# Schematic_EBook_v19.net
KiCad netlist of a schematic drawn in EAGLE
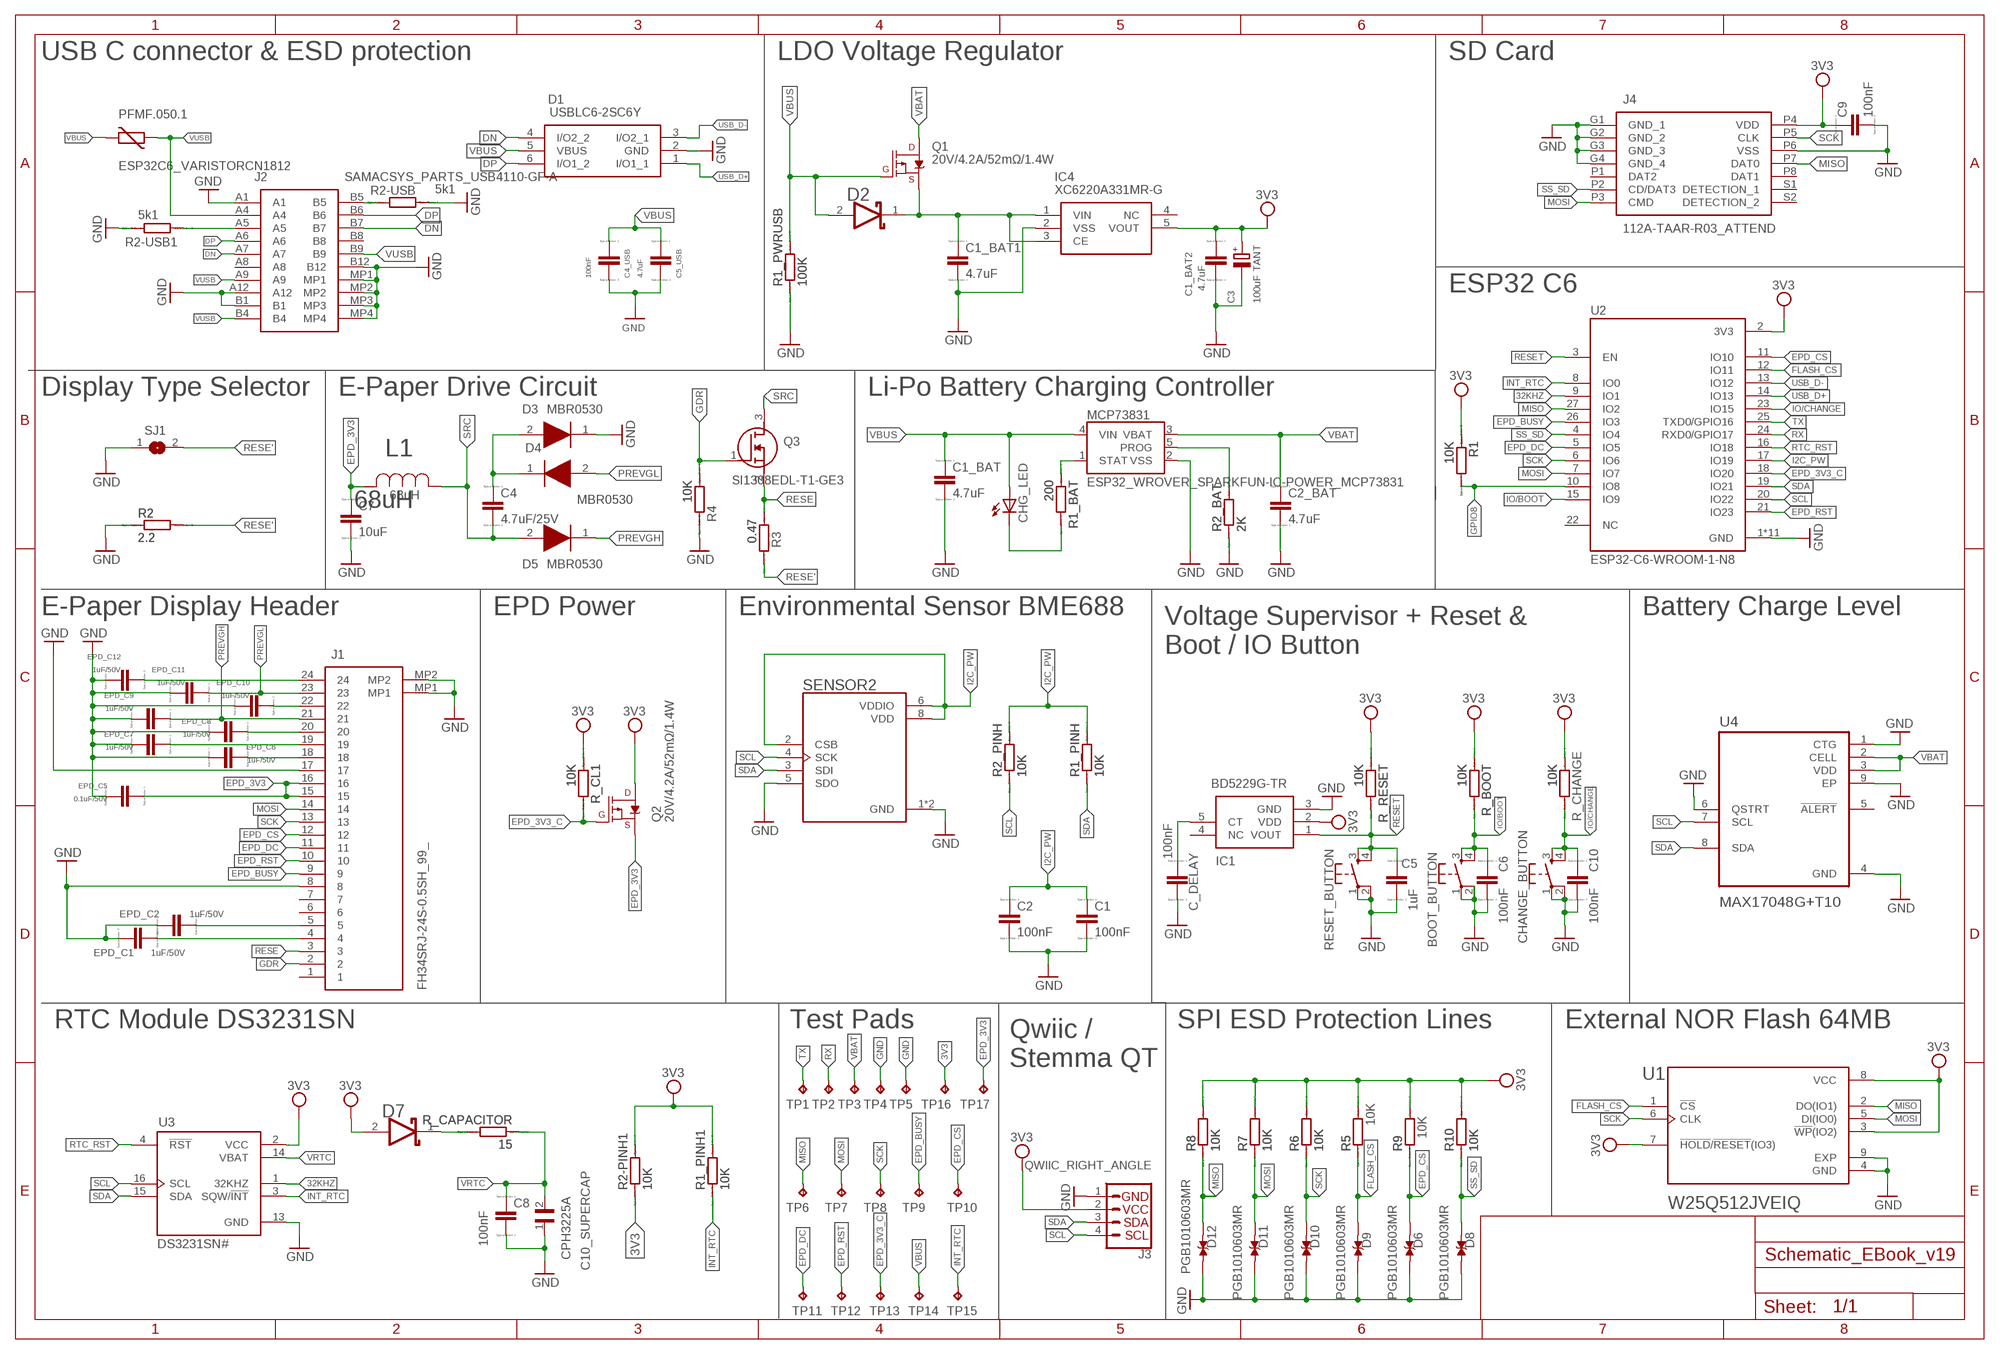
[diagram p0: schematic, sheet 1]

(export (version "E")
  (design (tool "Eeschema 10.0.6"))
  (components
    (comp (ref "BOOT_BUTTON")
      (value "BUTTON_CUSYOMV1")
      (footprint "eagle-import:MYBUTTON")
      (libsource (lib "eagle-import") (part "BUTTON_CUSYOMV1"))
    )
    (comp (ref "C1")
      (value "100nF")
      (footprint "eagle-import:EAGLE-LTSPICE_C0402")
      (libsource (lib "eagle-import") (part "EAGLE-LTSPICE_CC0402"))
    )
    (comp (ref "C1_BAT")
      (value "4.7uF")
      (footprint "eagle-import:EAGLE-LTSPICE_C0402")
      (libsource (lib "eagle-import") (part "EAGLE-LTSPICE_CC0402"))
    )
    (comp (ref "C1_BAT1")
      (value "4.7uF")
      (footprint "eagle-import:EAGLE-LTSPICE_C0402")
      (libsource (lib "eagle-import") (part "EAGLE-LTSPICE_CC0402"))
    )
    (comp (ref "C1_BAT2")
      (value "4.7uF")
      (footprint "eagle-import:EAGLE-LTSPICE_C0402")
      (libsource (lib "eagle-import") (part "ESP32_WROVER_EAGLE-LTSPICE_CC0402"))
    )
    (comp (ref "C2")
      (value "100nF")
      (footprint "eagle-import:EAGLE-LTSPICE_C0402")
      (libsource (lib "eagle-import") (part "EAGLE-LTSPICE_CC0402"))
    )
    (comp (ref "C2_BAT")
      (value "4.7uF")
      (footprint "eagle-import:EAGLE-LTSPICE_C0402")
      (libsource (lib "eagle-import") (part "EAGLE-LTSPICE_CC0402"))
    )
    (comp (ref "C3")
      (value "100uF TANT")
      (footprint "eagle-import:RCL_CT3528")
      (libsource (lib "eagle-import") (part "RCL_CPOL-EUCT3528"))
    )
    (comp (ref "C4")
      (value "4.7uF/25V")
      (footprint "eagle-import:EAGLE-LTSPICE_C0402")
      (libsource (lib "eagle-import") (part "EAGLE-LTSPICE_CC0402"))
    )
    (comp (ref "C4_USB")
      (value "100nF")
      (footprint "eagle-import:EAGLE-LTSPICE_C0402")
      (libsource (lib "eagle-import") (part "EAGLE-LTSPICE_CC0402"))
    )
    (comp (ref "C5")
      (value "1uF")
      (footprint "eagle-import:EAGLE-LTSPICE_C0402")
      (libsource (lib "eagle-import") (part "EAGLE-LTSPICE_CC0402"))
    )
    (comp (ref "C5_USB")
      (value "4.7uF")
      (footprint "eagle-import:EAGLE-LTSPICE_C0402")
      (libsource (lib "eagle-import") (part "EAGLE-LTSPICE_CC0402"))
    )
    (comp (ref "C6")
      (value "100nF")
      (footprint "eagle-import:EAGLE-LTSPICE_C0402")
      (libsource (lib "eagle-import") (part "EAGLE-LTSPICE_CC0402"))
    )
    (comp (ref "C7")
      (value "10uF")
      (footprint "eagle-import:EAGLE-LTSPICE_C0402")
      (libsource (lib "eagle-import") (part "EAGLE-LTSPICE_CC0402"))
    )
    (comp (ref "C8")
      (value "100nF")
      (footprint "eagle-import:EAGLE-LTSPICE_C0402")
      (libsource (lib "eagle-import") (part "EAGLE-LTSPICE_CC0402"))
    )
    (comp (ref "C9")
      (value "100nF")
      (footprint "eagle-import:EAGLE-LTSPICE_C0402")
      (libsource (lib "eagle-import") (part "EAGLE-LTSPICE_CC0402"))
    )
    (comp (ref "C10")
      (value "100nF")
      (footprint "eagle-import:EAGLE-LTSPICE_C0402")
      (libsource (lib "eagle-import") (part "EAGLE-LTSPICE_CC0402"))
    )
    (comp (ref "C10_SUPERCAP")
      (value "CPH3225A")
      (footprint "eagle-import:CAPCP3225X100N")
      (fields (field (name "MF") "Seiko Instruments"))
      (libsource (lib "eagle-import") (part "CPH3225A"))
    )
    (comp (ref "CHANGE_BUTTON")
      (value "BUTTON_CUSYOMV1")
      (footprint "eagle-import:MYBUTTON")
      (libsource (lib "eagle-import") (part "BUTTON_CUSYOMV1"))
    )
    (comp (ref "CHG_LED")
      (value "ADAFRUIT_LEDCHIP-LED0603")
      (footprint "eagle-import:ADAFRUIT_CHIP-LED0603")
      (libsource (lib "eagle-import") (part "ADAFRUIT_LEDCHIP-LED0603"))
    )
    (comp (ref "C_DELAY")
      (value "100nF")
      (footprint "eagle-import:EAGLE-LTSPICE_C0402")
      (libsource (lib "eagle-import") (part "EAGLE-LTSPICE_CC0402"))
    )
    (comp (ref "D1")
      (value "USBLC6-2SC6Y")
      (footprint "eagle-import:SOT95P280X145-6N")
      (fields (field (name "MF") "STMicroelectronics"))
      (libsource (lib "eagle-import") (part "USBLC6-2SC6Y"))
    )
    (comp (ref "D2")
      (value "ESP32_WROVER_AVX---SD0805S020S1R0_AVX_SD0805S020S1R0_0_0AVX_SD0805S020S1R0_0_0")
      (footprint "eagle-import:ESP32_WROVER_AVX---SD0805S020S1R0_AVX_SD0805S020S1R0_0")
      (fields
        (field (name "DIGIKEY_PART_NUMBER") "478-7800-1-ND")
        (field (name "MF") "AVX")
        (field (name "MOUSER_PART_NUMBER") "581-SD0805S020S1R0")
      )
      (libsource (lib "eagle-import") (part "ESP32_WROVER_AVX---SD0805S020S1R0_AVX_SD0805S020S1R0_0_0AVX_SD0805S020S1R0_0_0"))
    )
    (comp (ref "D3")
      (value "MBR0530")
      (footprint "eagle-import:SOD3716X135N")
      (fields (field (name "MF") "ON Semiconductor"))
      (libsource (lib "eagle-import") (part "MBR0530"))
    )
    (comp (ref "D4")
      (value "MBR0530")
      (footprint "eagle-import:SOD3716X135N")
      (fields (field (name "MF") "ON Semiconductor"))
      (libsource (lib "eagle-import") (part "MBR0530"))
    )
    (comp (ref "D5")
      (value "MBR0530")
      (footprint "eagle-import:SOD3716X135N")
      (fields (field (name "MF") "ON Semiconductor"))
      (libsource (lib "eagle-import") (part "MBR0530"))
    )
    (comp (ref "D6")
      (value "PGB1010603MR")
      (footprint "eagle-import:DIOC1608X36N")
      (fields (field (name "MF") "Littelfuse Inc."))
      (libsource (lib "eagle-import") (part "PGB1010603MR"))
    )
    (comp (ref "D7")
      (value "ESP32_WROVER_AVX---SD0805S020S1R0_AVX_SD0805S020S1R0_0_0AVX_SD0805S020S1R0_0_0")
      (footprint "eagle-import:ESP32_WROVER_AVX---SD0805S020S1R0_AVX_SD0805S020S1R0_0")
      (fields
        (field (name "DIGIKEY_PART_NUMBER") "478-7800-1-ND")
        (field (name "MF") "AVX")
        (field (name "MOUSER_PART_NUMBER") "581-SD0805S020S1R0")
      )
      (libsource (lib "eagle-import") (part "ESP32_WROVER_AVX---SD0805S020S1R0_AVX_SD0805S020S1R0_0_0AVX_SD0805S020S1R0_0_0"))
    )
    (comp (ref "D8")
      (value "PGB1010603MR")
      (footprint "eagle-import:DIOC1608X36N")
      (fields (field (name "MF") "Littelfuse Inc."))
      (libsource (lib "eagle-import") (part "PGB1010603MR"))
    )
    (comp (ref "D9")
      (value "PGB1010603MR")
      (footprint "eagle-import:DIOC1608X36N")
      (fields (field (name "MF") "Littelfuse Inc."))
      (libsource (lib "eagle-import") (part "PGB1010603MR"))
    )
    (comp (ref "D10")
      (value "PGB1010603MR")
      (footprint "eagle-import:DIOC1608X36N")
      (fields (field (name "MF") "Littelfuse Inc."))
      (libsource (lib "eagle-import") (part "PGB1010603MR"))
    )
    (comp (ref "D11")
      (value "PGB1010603MR")
      (footprint "eagle-import:DIOC1608X36N")
      (fields (field (name "MF") "Littelfuse Inc."))
      (libsource (lib "eagle-import") (part "PGB1010603MR"))
    )
    (comp (ref "D12")
      (value "PGB1010603MR")
      (footprint "eagle-import:DIOC1608X36N")
      (fields (field (name "MF") "Littelfuse Inc."))
      (libsource (lib "eagle-import") (part "PGB1010603MR"))
    )
    (comp (ref "EPD_C1")
      (value "1uF/50V")
      (footprint "eagle-import:EAGLE-LTSPICE_C0402")
      (libsource (lib "eagle-import") (part "EAGLE-LTSPICE_CC0402"))
    )
    (comp (ref "EPD_C2")
      (value "1uF/50V")
      (footprint "eagle-import:EAGLE-LTSPICE_C0402")
      (libsource (lib "eagle-import") (part "EAGLE-LTSPICE_CC0402"))
    )
    (comp (ref "EPD_C5")
      (value "0.1uF/50V")
      (footprint "eagle-import:EAGLE-LTSPICE_C0402")
      (libsource (lib "eagle-import") (part "EAGLE-LTSPICE_CC0402"))
    )
    (comp (ref "EPD_C6")
      (value "1uF/50V")
      (footprint "eagle-import:EAGLE-LTSPICE_C0402")
      (libsource (lib "eagle-import") (part "EAGLE-LTSPICE_CC0402"))
    )
    (comp (ref "EPD_C7")
      (value "1uF/50V")
      (footprint "eagle-import:EAGLE-LTSPICE_C0402")
      (libsource (lib "eagle-import") (part "EAGLE-LTSPICE_CC0402"))
    )
    (comp (ref "EPD_C8")
      (value "1uF/50V")
      (footprint "eagle-import:EAGLE-LTSPICE_C0402")
      (libsource (lib "eagle-import") (part "EAGLE-LTSPICE_CC0402"))
    )
    (comp (ref "EPD_C9")
      (value "1uF/50V")
      (footprint "eagle-import:EAGLE-LTSPICE_C0402")
      (libsource (lib "eagle-import") (part "EAGLE-LTSPICE_CC0402"))
    )
    (comp (ref "EPD_C10")
      (value "1uF/50V")
      (footprint "eagle-import:EAGLE-LTSPICE_C0402")
      (libsource (lib "eagle-import") (part "EAGLE-LTSPICE_CC0402"))
    )
    (comp (ref "EPD_C11")
      (value "1uF/50V")
      (footprint "eagle-import:EAGLE-LTSPICE_C0402")
      (libsource (lib "eagle-import") (part "EAGLE-LTSPICE_CC0402"))
    )
    (comp (ref "EPD_C12")
      (value "1uF/50V")
      (footprint "eagle-import:EAGLE-LTSPICE_C0402")
      (libsource (lib "eagle-import") (part "EAGLE-LTSPICE_CC0402"))
    )
    (comp (ref "IC1")
      (value "BD5229G-TR")
      (footprint "eagle-import:SOT95P280X125-5N")
      (fields (field (name "MOUSER_PART_NUMBER") "755-BD5229G-TR"))
      (libsource (lib "eagle-import") (part "BD5229G-TR"))
    )
    (comp (ref "IC4")
      (value "XC6220A331MR-G")
      (footprint "eagle-import:SOT95P280X120-5N")
      (fields (field (name "MOUSER_PART_NUMBER") "865-XC6220A331MR-G"))
      (libsource (lib "eagle-import") (part "XC6220A331MR-G"))
    )
    (comp (ref "J1")
      (value "FH34SRJ-24S-0.5SH_99_")
      (footprint "eagle-import:FH34SRJ24S05SH99")
      (fields
        (field (name "MANUFACTURER_PART_NUMBER") "FH34SRJ-24S-0.5SH(99)")
        (field (name "MOUSER_PART_NUMBER") "798-FH34SRJ24S05SH99")
      )
      (libsource (lib "eagle-import") (part "FH34SRJ-24S-0.5SH_99_"))
    )
    (comp (ref "J2")
      (value "SAMACSYS_PARTS_USB4110-GF-A")
      (footprint "eagle-import:SAMACSYS_PARTS_USB4110GFA")
      (fields
        (field (name "MANUFACTURER_PART_NUMBER") "USB4110-GF-A")
        (field (name "MOUSER_PART_NUMBER") "640-USB4110-GF-A")
      )
      (libsource (lib "eagle-import") (part "SAMACSYS_PARTS_USB4110-GF-A"))
    )
    (comp (ref "J3")
      (value "QWIIC_RIGHT_ANGLE")
      (footprint "eagle-import:JST04_1MM_RA")
      (libsource (lib "eagle-import") (part "QWIIC_CONNECTORJS-1MM"))
    )
    (comp (ref "J4")
      (value "112A-TAAR-R03_ATTEND")
      (footprint "eagle-import:112ATAARR03ATTEND")
      (fields (field (name "MANUFACTURER_PART_NUMBER") "112A-TAAR-R03 ATTEND"))
      (libsource (lib "eagle-import") (part "112A-TAAR-R03_ATTEND"))
    )
    (comp (ref "L1")
      (value "68uH")
      (footprint "eagle-import:IND_4828-WE-TPC_WRE")
      (fields
        (field (name "MANUFACTURER_PART_NUMBER") "744043680")
        (field (name "COPYRIGHT") "Copyright (C) 2024 Ultra Librarian. All rights reserved.")
      )
      (libsource (lib "eagle-import") (part "744043680IND_4828-WE-TPC_WRE"))
    )
    (comp (ref "MCP73831")
      (value "ESP32_WROVER_SPARKFUN-IC-POWER_MCP73831")
      (footprint "eagle-import:ESP32_WROVER_SPARKFUN-IC-POWER_SOT23-5")
      (libsource (lib "eagle-import") (part "ESP32_WROVER_SPARKFUN-IC-POWER_MCP73831"))
    )
    (comp (ref "PFMF.050.1")
      (value "ESP32C6_VARISTORCN1812")
      (footprint "eagle-import:ESP32C6_VARISTOR_CT_CN1812")
      (libsource (lib "eagle-import") (part "ESP32C6_VARISTORCN1812"))
    )
    (comp (ref "Q1")
      (value "20V/4.2A/52mΩ/1.4W")
      (footprint "eagle-import:ESP32_WROVER_SPARKFUN-DISCRETESEMI_SOT23-3")
      (libsource (lib "eagle-import") (part "ESP32_WROVER_SPARKFUN-DISCRETESEMI_MOSFET_PCH-DMG2305UX-7"))
    )
    (comp (ref "Q2")
      (value "20V/4.2A/52mΩ/1.4W")
      (footprint "eagle-import:ESP32_WROVER_SPARKFUN-DISCRETESEMI_SOT23-3")
      (libsource (lib "eagle-import") (part "ESP32_WROVER_SPARKFUN-DISCRETESEMI_MOSFET_PCH-DMG2305UX-7"))
    )
    (comp (ref "Q3")
      (value "SI1308EDL-T1-GE3")
      (footprint "eagle-import:SOT65P210X110-3N")
      (fields (field (name "MF") "Vishay Siliconix"))
      (libsource (lib "eagle-import") (part "SI1308EDL-T1-GE3"))
    )
    (comp (ref "R1")
      (value "10K")
      (footprint "eagle-import:ESP32_WROVER_EAGLE-LTSPICE_R0402")
      (libsource (lib "eagle-import") (part "ESP32_WROVER_EAGLE-LTSPICE_RR0402"))
    )
    (comp (ref "R1_BAT")
      (value "200")
      (footprint "eagle-import:ESP32_WROVER_EAGLE-LTSPICE_R0402")
      (libsource (lib "eagle-import") (part "ESP32_WROVER_EAGLE-LTSPICE_RR0402"))
    )
    (comp (ref "R1_PINH")
      (value "10K")
      (footprint "eagle-import:ESP32_WROVER_EAGLE-LTSPICE_R0402")
      (libsource (lib "eagle-import") (part "ESP32_WROVER_EAGLE-LTSPICE_RR0402"))
    )
    (comp (ref "R1_PINH1")
      (value "10K")
      (footprint "eagle-import:ESP32_WROVER_EAGLE-LTSPICE_R0402")
      (libsource (lib "eagle-import") (part "ESP32_WROVER_EAGLE-LTSPICE_RR0402"))
    )
    (comp (ref "R1_PWRUSB")
      (value "100K")
      (footprint "eagle-import:ESP32_WROVER_EAGLE-LTSPICE_R0402")
      (libsource (lib "eagle-import") (part "ESP32_WROVER_EAGLE-LTSPICE_RR0402"))
    )
    (comp (ref "R2")
      (value "2.2")
      (footprint "eagle-import:ESP32_WROVER_EAGLE-LTSPICE_R0402")
      (libsource (lib "eagle-import") (part "ESP32_WROVER_EAGLE-LTSPICE_RR0402"))
    )
    (comp (ref "R2-PINH1")
      (value "10K")
      (footprint "eagle-import:ESP32_WROVER_EAGLE-LTSPICE_R0402")
      (libsource (lib "eagle-import") (part "ESP32_WROVER_EAGLE-LTSPICE_RR0402"))
    )
    (comp (ref "R2-USB")
      (value "5k1")
      (footprint "eagle-import:ESP32_WROVER_EAGLE-LTSPICE_R0402")
      (libsource (lib "eagle-import") (part "ESP32_WROVER_EAGLE-LTSPICE_RR0402"))
    )
    (comp (ref "R2-USB1")
      (value "5k1")
      (footprint "eagle-import:ESP32_WROVER_EAGLE-LTSPICE_R0402")
      (libsource (lib "eagle-import") (part "ESP32_WROVER_EAGLE-LTSPICE_RR0402"))
    )
    (comp (ref "R2_BAT")
      (value "2K")
      (footprint "eagle-import:ESP32_WROVER_EAGLE-LTSPICE_R0402")
      (libsource (lib "eagle-import") (part "ESP32_WROVER_EAGLE-LTSPICE_RR0402"))
    )
    (comp (ref "R2_PINH")
      (value "10K")
      (footprint "eagle-import:ESP32_WROVER_EAGLE-LTSPICE_R0402")
      (libsource (lib "eagle-import") (part "ESP32_WROVER_EAGLE-LTSPICE_RR0402"))
    )
    (comp (ref "R3")
      (value "0.47")
      (footprint "eagle-import:ESP32_WROVER_EAGLE-LTSPICE_R0402")
      (libsource (lib "eagle-import") (part "ESP32_WROVER_EAGLE-LTSPICE_RR0402"))
    )
    (comp (ref "R4")
      (value "10K")
      (footprint "eagle-import:ESP32_WROVER_EAGLE-LTSPICE_R0402")
      (libsource (lib "eagle-import") (part "ESP32_WROVER_EAGLE-LTSPICE_RR0402"))
    )
    (comp (ref "R5")
      (value "10K")
      (footprint "eagle-import:ESP32_WROVER_EAGLE-LTSPICE_R0402")
      (libsource (lib "eagle-import") (part "ESP32_WROVER_EAGLE-LTSPICE_RR0402"))
    )
    (comp (ref "R6")
      (value "10K")
      (footprint "eagle-import:ESP32_WROVER_EAGLE-LTSPICE_R0402")
      (libsource (lib "eagle-import") (part "ESP32_WROVER_EAGLE-LTSPICE_RR0402"))
    )
    (comp (ref "R7")
      (value "10K")
      (footprint "eagle-import:ESP32_WROVER_EAGLE-LTSPICE_R0402")
      (libsource (lib "eagle-import") (part "ESP32_WROVER_EAGLE-LTSPICE_RR0402"))
    )
    (comp (ref "R8")
      (value "10K")
      (footprint "eagle-import:ESP32_WROVER_EAGLE-LTSPICE_R0402")
      (libsource (lib "eagle-import") (part "ESP32_WROVER_EAGLE-LTSPICE_RR0402"))
    )
    (comp (ref "R9")
      (value "10K")
      (footprint "eagle-import:ESP32_WROVER_EAGLE-LTSPICE_R0402")
      (libsource (lib "eagle-import") (part "ESP32_WROVER_EAGLE-LTSPICE_RR0402"))
    )
    (comp (ref "R10")
      (value "10K")
      (footprint "eagle-import:ESP32_WROVER_EAGLE-LTSPICE_R0402")
      (libsource (lib "eagle-import") (part "ESP32_WROVER_EAGLE-LTSPICE_RR0402"))
    )
    (comp (ref "RESET_BUTTON")
      (value "BUTTON_CUSYOMV1")
      (footprint "eagle-import:MYBUTTON")
      (libsource (lib "eagle-import") (part "BUTTON_CUSYOMV1"))
    )
    (comp (ref "R_BOOT")
      (value "10K")
      (footprint "eagle-import:ESP32_WROVER_EAGLE-LTSPICE_R0402")
      (libsource (lib "eagle-import") (part "ESP32_WROVER_EAGLE-LTSPICE_RR0402"))
    )
    (comp (ref "R_CAPACITOR")
      (value "15")
      (footprint "eagle-import:ESP32_WROVER_EAGLE-LTSPICE_R0402")
      (libsource (lib "eagle-import") (part "ESP32_WROVER_EAGLE-LTSPICE_RR0402"))
    )
    (comp (ref "R_CHANGE")
      (value "10K")
      (footprint "eagle-import:ESP32_WROVER_EAGLE-LTSPICE_R0402")
      (libsource (lib "eagle-import") (part "ESP32_WROVER_EAGLE-LTSPICE_RR0402"))
    )
    (comp (ref "R_CL1")
      (value "10K")
      (footprint "eagle-import:ESP32_WROVER_EAGLE-LTSPICE_R0402")
      (libsource (lib "eagle-import") (part "ESP32_WROVER_EAGLE-LTSPICE_RR0402"))
    )
    (comp (ref "R_RESET")
      (value "10K")
      (footprint "eagle-import:ESP32_WROVER_EAGLE-LTSPICE_R0402")
      (libsource (lib "eagle-import") (part "ESP32_WROVER_EAGLE-LTSPICE_RR0402"))
    )
    (comp (ref "SENSOR2")
      (value "ESP32_WROVER_BME680_BME680")
      (footprint "eagle-import:ESP32_WROVER_BME680_PSON80P300X300X100-8N")
      (fields (field (name "MF") "Bosch Sensortec") (field (name "MP") "BME680"))
      (libsource (lib "eagle-import") (part "ESP32_WROVER_BME680_BME680"))
    )
    (comp (ref "SJ1") (value "SJ") (footprint "eagle-import:SJ") (libsource (lib "eagle-import") (part "SJ")))
    (comp (ref "TP1")
      (value "TPTP20R")
      (footprint "eagle-import:TP20R")
      (libsource (lib "eagle-import") (part "TPTP20R"))
    )
    (comp (ref "TP2")
      (value "TPTP20R")
      (footprint "eagle-import:TP20R")
      (libsource (lib "eagle-import") (part "TPTP20R"))
    )
    (comp (ref "TP3")
      (value "TPTP20R")
      (footprint "eagle-import:TP20R")
      (libsource (lib "eagle-import") (part "TPTP20R"))
    )
    (comp (ref "TP4")
      (value "TPTP20R")
      (footprint "eagle-import:TP20R")
      (libsource (lib "eagle-import") (part "TPTP20R"))
    )
    (comp (ref "TP5")
      (value "TPTP20R")
      (footprint "eagle-import:TP20R")
      (libsource (lib "eagle-import") (part "TPTP20R"))
    )
    (comp (ref "TP6")
      (value "TPTP20R")
      (footprint "eagle-import:TP20R")
      (libsource (lib "eagle-import") (part "TPTP20R"))
    )
    (comp (ref "TP7")
      (value "TPTP20R")
      (footprint "eagle-import:TP20R")
      (libsource (lib "eagle-import") (part "TPTP20R"))
    )
    (comp (ref "TP8")
      (value "TPTP20R")
      (footprint "eagle-import:TP20R")
      (libsource (lib "eagle-import") (part "TPTP20R"))
    )
    (comp (ref "TP9")
      (value "TPTP20R")
      (footprint "eagle-import:TP20R")
      (libsource (lib "eagle-import") (part "TPTP20R"))
    )
    (comp (ref "TP10")
      (value "TPTP20R")
      (footprint "eagle-import:TP20R")
      (libsource (lib "eagle-import") (part "TPTP20R"))
    )
    (comp (ref "TP11")
      (value "TPTP20R")
      (footprint "eagle-import:TP20R")
      (libsource (lib "eagle-import") (part "TPTP20R"))
    )
    (comp (ref "TP12")
      (value "TPTP20R")
      (footprint "eagle-import:TP20R")
      (libsource (lib "eagle-import") (part "TPTP20R"))
    )
    (comp (ref "TP13")
      (value "TPTP20R")
      (footprint "eagle-import:TP20R")
      (libsource (lib "eagle-import") (part "TPTP20R"))
    )
    (comp (ref "TP14")
      (value "TPTP20R")
      (footprint "eagle-import:TP20R")
      (libsource (lib "eagle-import") (part "TPTP20R"))
    )
    (comp (ref "TP15")
      (value "TPTP20R")
      (footprint "eagle-import:TP20R")
      (libsource (lib "eagle-import") (part "TPTP20R"))
    )
    (comp (ref "TP16")
      (value "TPTP20R")
      (footprint "eagle-import:TP20R")
      (libsource (lib "eagle-import") (part "TPTP20R"))
    )
    (comp (ref "TP17")
      (value "TPTP20R")
      (footprint "eagle-import:TP20R")
      (libsource (lib "eagle-import") (part "TPTP20R"))
    )
    (comp (ref "U1")
      (value "W25Q512JVEIQ")
      (footprint "eagle-import:SON127P600X800X80-9N")
      (fields (field (name "MF") "Winbond Electronics"))
      (libsource (lib "eagle-import") (part "W25Q512JVEIQ"))
    )
    (comp (ref "U2")
      (value "ESP32-C6-WROOM-1-N8")
      (footprint "eagle-import:XCVR_ESP32-C6-WROOM-1-N8")
      (fields (field (name "MF") "Espressif Systems"))
      (libsource (lib "eagle-import") (part "ESP32-C6-WROOM-1-N8"))
    )
    (comp (ref "U3")
      (value "DS3231SN#")
      (footprint "eagle-import:SOIC127P1032X265-16N")
      (fields (field (name "MF") "Analog Devices"))
      (libsource (lib "eagle-import") (part "DS3231SN#"))
    )
    (comp (ref "U4")
      (value "MAX17048G+T10")
      (footprint "eagle-import:SON50P200X200X80-9N")
      (fields (field (name "MF") "Analog Devices"))
      (libsource (lib "eagle-import") (part "MAX17048G+T10"))
    )
  )
  (nets
    (net (code "1") (name "3V3") (class "Default")
      (node (ref "C1_BAT2") (pin "1") (pinfunction "1_1") (pintype "passive"))
      (node (ref "C3") (pin "+") (pinfunction "+_+") (pintype "passive"))
      (node (ref "C9") (pin "1") (pinfunction "1_1") (pintype "passive"))
      (node (ref "D7") (pin "2") (pinfunction "ANODE_2") (pintype "bidirectional"))
      (node (ref "IC1") (pin "2") (pinfunction "VDD_2") (pintype "bidirectional"))
      (node (ref "IC4") (pin "5") (pinfunction "VOUT_5") (pintype "bidirectional"))
      (node (ref "J3") (pin "2") (pinfunction "2_2") (pintype "power_in"))
      (node (ref "J4") (pin "P4") (pinfunction "VDD_P4") (pintype "bidirectional"))
      (node (ref "Q2") (pin "3") (pinfunction "D_3") (pintype "bidirectional"))
      (node (ref "R1") (pin "1") (pinfunction "1_1") (pintype "passive"))
      (node (ref "R10") (pin "2") (pinfunction "2_2") (pintype "passive"))
      (node (ref "R1_PINH1") (pin "2") (pinfunction "2_2") (pintype "passive"))
      (node (ref "R2-PINH1") (pin "1") (pinfunction "1_1") (pintype "passive"))
      (node (ref "R2-PINH1") (pin "2") (pinfunction "2_2") (pintype "passive"))
      (node (ref "R5") (pin "2") (pinfunction "2_2") (pintype "passive"))
      (node (ref "R6") (pin "2") (pinfunction "2_2") (pintype "passive"))
      (node (ref "R7") (pin "2") (pinfunction "2_2") (pintype "passive"))
      (node (ref "R8") (pin "2") (pinfunction "2_2") (pintype "passive"))
      (node (ref "R9") (pin "2") (pinfunction "2_2") (pintype "passive"))
      (node (ref "R_BOOT") (pin "1") (pinfunction "1_1") (pintype "passive"))
      (node (ref "R_CHANGE") (pin "1") (pinfunction "1_1") (pintype "passive"))
      (node (ref "R_CL1") (pin "1") (pinfunction "1_1") (pintype "passive"))
      (node (ref "R_RESET") (pin "1") (pinfunction "1_1") (pintype "passive"))
      (node (ref "TP16") (pin "TP") (pinfunction "TP_TP") (pintype "input"))
      (node (ref "U1") (pin "3") (pinfunction "~{WP}(IO2)_3") (pintype "bidirectional"))
      (node (ref "U1") (pin "7") (pinfunction "~{HOLD}/~{RESET}(IO3)_7") (pintype "bidirectional"))
      (node (ref "U1") (pin "8") (pinfunction "VCC_8") (pintype "power_in"))
      (node (ref "U2") (pin "2") (pinfunction "3V3_2") (pintype "power_in"))
      (node (ref "U3") (pin "2") (pinfunction "VCC_2") (pintype "power_in"))
    )
    (net (code "2") (name "32KHZ") (class "Default")
      (node (ref "U2") (pin "9") (pinfunction "IO1_9") (pintype "bidirectional"))
      (node (ref "U3") (pin "1") (pinfunction "32KHZ_1") (pintype "output"))
    )
    (net (code "3") (name "DN") (class "Default")
      (node (ref "D1") (pin "4") (pinfunction "I/O2_2_4") (pintype "bidirectional"))
      (node (ref "J2") (pin "A7") (pinfunction "A7_A7") (pintype "bidirectional"))
      (node (ref "J2") (pin "B7") (pinfunction "B7_B7") (pintype "bidirectional"))
    )
    (net (code "4") (name "DP") (class "Default")
      (node (ref "D1") (pin "6") (pinfunction "I/O1_2_6") (pintype "bidirectional"))
      (node (ref "J2") (pin "A6") (pinfunction "A6_A6") (pintype "bidirectional"))
      (node (ref "J2") (pin "B6") (pinfunction "B6_B6") (pintype "bidirectional"))
    )
    (net (code "5") (name "EPD_3V3") (class "Default")
      (node (ref "C7") (pin "1") (pinfunction "1_1") (pintype "passive"))
      (node (ref "EPD_C5") (pin "1") (pinfunction "1_1") (pintype "passive"))
      (node (ref "J1") (pin "15") (pinfunction "15_15") (pintype "bidirectional"))
      (node (ref "J1") (pin "16") (pinfunction "16_16") (pintype "bidirectional"))
      (node (ref "L1") (pin "2") (pinfunction "2_2") (pintype "passive"))
      (node (ref "Q2") (pin "2") (pinfunction "S_2") (pintype "bidirectional"))
      (node (ref "TP17") (pin "TP") (pinfunction "TP_TP") (pintype "input"))
    )
    (net (code "6") (name "EPD_3V3_C") (class "Default")
      (node (ref "Q2") (pin "1") (pinfunction "G_1") (pintype "bidirectional"))
      (node (ref "R_CL1") (pin "2") (pinfunction "2_2") (pintype "passive"))
      (node (ref "TP13") (pin "TP") (pinfunction "TP_TP") (pintype "input"))
      (node (ref "U2") (pin "18") (pinfunction "IO20_18") (pintype "bidirectional"))
    )
    (net (code "7") (name "EPD_BUSY") (class "Default")
      (node (ref "J1") (pin "9") (pinfunction "9_9") (pintype "bidirectional"))
      (node (ref "TP9") (pin "TP") (pinfunction "TP_TP") (pintype "input"))
      (node (ref "U2") (pin "26") (pinfunction "IO3_26") (pintype "bidirectional"))
    )
    (net (code "8") (name "EPD_CS") (class "Default")
      (node (ref "D6") (pin "2") (pinfunction "2_2") (pintype "passive"))
      (node (ref "J1") (pin "12") (pinfunction "12_12") (pintype "bidirectional"))
      (node (ref "R9") (pin "1") (pinfunction "1_1") (pintype "passive"))
      (node (ref "TP10") (pin "TP") (pinfunction "TP_TP") (pintype "input"))
      (node (ref "U2") (pin "11") (pinfunction "IO10_11") (pintype "bidirectional"))
    )
    (net (code "9") (name "EPD_DC") (class "Default")
      (node (ref "J1") (pin "11") (pinfunction "11_11") (pintype "bidirectional"))
      (node (ref "TP11") (pin "TP") (pinfunction "TP_TP") (pintype "input"))
      (node (ref "U2") (pin "5") (pinfunction "IO5_5") (pintype "bidirectional"))
    )
    (net (code "10") (name "EPD_RST") (class "Default")
      (node (ref "J1") (pin "10") (pinfunction "10_10") (pintype "bidirectional"))
      (node (ref "TP12") (pin "TP") (pinfunction "TP_TP") (pintype "input"))
      (node (ref "U2") (pin "21") (pinfunction "IO23_21") (pintype "bidirectional"))
    )
    (net (code "11") (name "FLASH_CS") (class "Default")
      (node (ref "D9") (pin "2") (pinfunction "2_2") (pintype "passive"))
      (node (ref "R5") (pin "1") (pinfunction "1_1") (pintype "passive"))
      (node (ref "U1") (pin "1") (pinfunction "~{CS}_1") (pintype "input"))
      (node (ref "U2") (pin "12") (pinfunction "IO11_12") (pintype "bidirectional"))
    )
    (net (code "12") (name "GDR") (class "Default")
      (node (ref "J1") (pin "2") (pinfunction "2_2") (pintype "bidirectional"))
      (node (ref "Q3") (pin "1") (pinfunction "G_1") (pintype "bidirectional"))
      (node (ref "R4") (pin "1") (pinfunction "1_1") (pintype "passive"))
    )
    (net (code "13") (name "GND") (class "Default")
      (node (ref "BOOT_BUTTON") (pin "1") (pinfunction "1_1") (pintype "passive"))
      (node (ref "BOOT_BUTTON") (pin "2") (pinfunction "2_2") (pintype "passive"))
      (node (ref "C1") (pin "2") (pinfunction "2_2") (pintype "passive"))
      (node (ref "C10") (pin "2") (pinfunction "2_2") (pintype "passive"))
      (node (ref "C10_SUPERCAP") (pin "1") (pinfunction "1_1") (pintype "passive"))
      (node (ref "C1_BAT") (pin "2") (pinfunction "2_2") (pintype "passive"))
      (node (ref "C1_BAT1") (pin "2") (pinfunction "2_2") (pintype "passive"))
      (node (ref "C1_BAT2") (pin "2") (pinfunction "2_2") (pintype "passive"))
      (node (ref "C2") (pin "2") (pinfunction "2_2") (pintype "passive"))
      (node (ref "C2_BAT") (pin "2") (pinfunction "2_2") (pintype "passive"))
      (node (ref "C3") (pin "-") (pinfunction "-_-") (pintype "passive"))
      (node (ref "C4_USB") (pin "2") (pinfunction "2_2") (pintype "passive"))
      (node (ref "C5") (pin "2") (pinfunction "2_2") (pintype "passive"))
      (node (ref "C5_USB") (pin "2") (pinfunction "2_2") (pintype "passive"))
      (node (ref "C6") (pin "2") (pinfunction "2_2") (pintype "passive"))
      (node (ref "C7") (pin "2") (pinfunction "2_2") (pintype "passive"))
      (node (ref "C8") (pin "2") (pinfunction "2_2") (pintype "passive"))
      (node (ref "C9") (pin "2") (pinfunction "2_2") (pintype "passive"))
      (node (ref "CHANGE_BUTTON") (pin "1") (pinfunction "1_1") (pintype "passive"))
      (node (ref "CHANGE_BUTTON") (pin "2") (pinfunction "2_2") (pintype "passive"))
      (node (ref "C_DELAY") (pin "2") (pinfunction "2_2") (pintype "passive"))
      (node (ref "D1") (pin "2") (pinfunction "GND_2") (pintype "bidirectional"))
      (node (ref "D10") (pin "1") (pinfunction "1_1") (pintype "passive"))
      (node (ref "D11") (pin "1") (pinfunction "1_1") (pintype "passive"))
      (node (ref "D12") (pin "1") (pinfunction "1_1") (pintype "passive"))
      (node (ref "D3") (pin "1") (pinfunction "K_1") (pintype "bidirectional"))
      (node (ref "D6") (pin "1") (pinfunction "1_1") (pintype "passive"))
      (node (ref "D8") (pin "1") (pinfunction "1_1") (pintype "passive"))
      (node (ref "D9") (pin "1") (pinfunction "1_1") (pintype "passive"))
      (node (ref "EPD_C1") (pin "2") (pinfunction "2_2") (pintype "passive"))
      (node (ref "EPD_C10") (pin "2") (pinfunction "2_2") (pintype "passive"))
      (node (ref "EPD_C11") (pin "2") (pinfunction "2_2") (pintype "passive"))
      (node (ref "EPD_C12") (pin "2") (pinfunction "2_2") (pintype "passive"))
      (node (ref "EPD_C2") (pin "2") (pinfunction "2_2") (pintype "passive"))
      (node (ref "EPD_C5") (pin "2") (pinfunction "2_2") (pintype "passive"))
      (node (ref "EPD_C6") (pin "2") (pinfunction "2_2") (pintype "passive"))
      (node (ref "EPD_C7") (pin "2") (pinfunction "2_2") (pintype "passive"))
      (node (ref "EPD_C8") (pin "2") (pinfunction "2_2") (pintype "passive"))
      (node (ref "EPD_C9") (pin "2") (pinfunction "2_2") (pintype "passive"))
      (node (ref "IC1") (pin "3") (pinfunction "GND_3") (pintype "bidirectional"))
      (node (ref "IC4") (pin "2") (pinfunction "VSS_2") (pintype "bidirectional"))
      (node (ref "J1") (pin "17") (pinfunction "17_17") (pintype "bidirectional"))
      (node (ref "J1") (pin "8") (pinfunction "8_8") (pintype "bidirectional"))
      (node (ref "J1") (pin "MP1") (pinfunction "MP1_MP1") (pintype "bidirectional"))
      (node (ref "J1") (pin "MP2") (pinfunction "MP2_MP2") (pintype "bidirectional"))
      (node (ref "J2") (pin "A1") (pinfunction "A1_A1") (pintype "bidirectional"))
      (node (ref "J2") (pin "A12") (pinfunction "A12_A12") (pintype "bidirectional"))
      (node (ref "J2") (pin "B1") (pinfunction "B1_B1") (pintype "bidirectional"))
      (node (ref "J2") (pin "B12") (pinfunction "B12_B12") (pintype "bidirectional"))
      (node (ref "J2") (pin "MP1") (pinfunction "MP1_MP1") (pintype "bidirectional"))
      (node (ref "J2") (pin "MP2") (pinfunction "MP2_MP2") (pintype "bidirectional"))
      (node (ref "J2") (pin "MP3") (pinfunction "MP3_MP3") (pintype "bidirectional"))
      (node (ref "J2") (pin "MP4") (pinfunction "MP4_MP4") (pintype "bidirectional"))
      (node (ref "J3") (pin "1") (pinfunction "1_1") (pintype "power_in"))
      (node (ref "J4") (pin "G1") (pinfunction "GND_1_G1") (pintype "bidirectional"))
      (node (ref "J4") (pin "G2") (pinfunction "GND_2_G2") (pintype "bidirectional"))
      (node (ref "J4") (pin "G3") (pinfunction "GND_3_G3") (pintype "bidirectional"))
      (node (ref "J4") (pin "G4") (pinfunction "GND_4_G4") (pintype "bidirectional"))
      (node (ref "J4") (pin "P6") (pinfunction "VSS_P6") (pintype "bidirectional"))
      (node (ref "MCP73831") (pin "2") (pinfunction "VSS_2") (pintype "power_in"))
      (node (ref "R1_PWRUSB") (pin "1") (pinfunction "1_1") (pintype "passive"))
      (node (ref "R2") (pin "1") (pinfunction "1_1") (pintype "passive"))
      (node (ref "R2-USB") (pin "2") (pinfunction "2_2") (pintype "passive"))
      (node (ref "R2-USB1") (pin "1") (pinfunction "1_1") (pintype "passive"))
      (node (ref "R2_BAT") (pin "1") (pinfunction "1_1") (pintype "passive"))
      (node (ref "R4") (pin "2") (pinfunction "2_2") (pintype "passive"))
      (node (ref "RESET_BUTTON") (pin "1") (pinfunction "1_1") (pintype "passive"))
      (node (ref "RESET_BUTTON") (pin "2") (pinfunction "2_2") (pintype "passive"))
      (node (ref "SENSOR2") (pin "1") (pinfunction "GND_1") (pintype "power_in"))
      (node (ref "SENSOR2") (pin "5") (pinfunction "SDO_5") (pintype "bidirectional"))
      (node (ref "SENSOR2") (pin "7") (pinfunction "GND_7") (pintype "power_in"))
      (node (ref "SJ1") (pin "1") (pinfunction "1_1") (pintype "passive"))
      (node (ref "TP4") (pin "TP") (pinfunction "TP_TP") (pintype "input"))
      (node (ref "TP5") (pin "TP") (pinfunction "TP_TP") (pintype "input"))
      (node (ref "U1") (pin "4") (pinfunction "GND_4") (pintype "power_in"))
      (node (ref "U1") (pin "9") (pinfunction "EXP_9") (pintype "passive"))
      (node (ref "U2") (pin "1") (pinfunction "GND_1") (pintype "power_in"))
      (node (ref "U2") (pin "28") (pinfunction "GND_28") (pintype "power_in"))
      (node (ref "U2") (pin "29_1") (pinfunction "GND_29_1") (pintype "power_in"))
      (node (ref "U2") (pin "29_2") (pinfunction "GND_29_2") (pintype "power_in"))
      (node (ref "U2") (pin "29_3") (pinfunction "GND_29_3") (pintype "power_in"))
      (node (ref "U2") (pin "29_4") (pinfunction "GND_29_4") (pintype "power_in"))
      (node (ref "U2") (pin "29_5") (pinfunction "GND_29_5") (pintype "power_in"))
      (node (ref "U2") (pin "29_6") (pinfunction "GND_29_6") (pintype "power_in"))
      (node (ref "U2") (pin "29_7") (pinfunction "GND_29_7") (pintype "power_in"))
      (node (ref "U2") (pin "29_8") (pinfunction "GND_29_8") (pintype "power_in"))
      (node (ref "U2") (pin "29_9") (pinfunction "GND_29_9") (pintype "power_in"))
      (node (ref "U3") (pin "13") (pinfunction "GND_13") (pintype "power_in"))
      (node (ref "U4") (pin "1") (pinfunction "CTG_1") (pintype "power_in"))
      (node (ref "U4") (pin "4") (pinfunction "GND_4") (pintype "power_in"))
      (node (ref "U4") (pin "6") (pinfunction "QSTRT_6") (pintype "input"))
      (node (ref "U4") (pin "9") (pinfunction "EP_9") (pintype "power_in"))
    )
    (net (code "14") (name "GPIO8") (class "Default")
      (node (ref "R1") (pin "2") (pinfunction "2_2") (pintype "passive"))
      (node (ref "U2") (pin "10") (pinfunction "IO8_10") (pintype "bidirectional"))
    )
    (net (code "15") (name "I2C_PW") (class "Default")
      (node (ref "C1") (pin "1") (pinfunction "1_1") (pintype "passive"))
      (node (ref "C2") (pin "1") (pinfunction "1_1") (pintype "passive"))
      (node (ref "R1_PINH") (pin "2") (pinfunction "2_2") (pintype "passive"))
      (node (ref "R2_PINH") (pin "2") (pinfunction "2_2") (pintype "passive"))
      (node (ref "SENSOR2") (pin "2") (pinfunction "CSB_2") (pintype "input"))
      (node (ref "SENSOR2") (pin "6") (pinfunction "VDDIO_6") (pintype "power_in"))
      (node (ref "SENSOR2") (pin "8") (pinfunction "VDD_8") (pintype "power_in"))
      (node (ref "U2") (pin "17") (pinfunction "IO19_17") (pintype "bidirectional"))
    )
    (net (code "16") (name "INT_RTC") (class "Default")
      (node (ref "R1_PINH1") (pin "1") (pinfunction "1_1") (pintype "passive"))
      (node (ref "TP15") (pin "TP") (pinfunction "TP_TP") (pintype "input"))
      (node (ref "U2") (pin "8") (pinfunction "IO0_8") (pintype "bidirectional"))
      (node (ref "U3") (pin "3") (pinfunction "SQW/~{INT}_3") (pintype "output"))
    )
    (net (code "17") (name "IO{slash}BOOT") (class "Default")
      (node (ref "BOOT_BUTTON") (pin "3") (pinfunction "3_3") (pintype "passive"))
      (node (ref "BOOT_BUTTON") (pin "4") (pinfunction "4_4") (pintype "passive"))
      (node (ref "C6") (pin "1") (pinfunction "1_1") (pintype "passive"))
      (node (ref "R_BOOT") (pin "2") (pinfunction "2_2") (pintype "passive"))
      (node (ref "U2") (pin "15") (pinfunction "IO9_15") (pintype "bidirectional"))
    )
    (net (code "18") (name "IO{slash}CHANGE") (class "Default")
      (node (ref "C10") (pin "1") (pinfunction "1_1") (pintype "passive"))
      (node (ref "CHANGE_BUTTON") (pin "3") (pinfunction "3_3") (pintype "passive"))
      (node (ref "CHANGE_BUTTON") (pin "4") (pinfunction "4_4") (pintype "passive"))
      (node (ref "R_CHANGE") (pin "2") (pinfunction "2_2") (pintype "passive"))
      (node (ref "U2") (pin "23") (pinfunction "IO15_23") (pintype "bidirectional"))
    )
    (net (code "19") (name "MISO") (class "Default")
      (node (ref "D12") (pin "2") (pinfunction "2_2") (pintype "passive"))
      (node (ref "J4") (pin "P7") (pinfunction "DAT0_P7") (pintype "bidirectional"))
      (node (ref "R8") (pin "1") (pinfunction "1_1") (pintype "passive"))
      (node (ref "TP6") (pin "TP") (pinfunction "TP_TP") (pintype "input"))
      (node (ref "U1") (pin "2") (pinfunction "DO(IO1)_2") (pintype "bidirectional"))
      (node (ref "U2") (pin "27") (pinfunction "IO2_27") (pintype "bidirectional"))
    )
    (net (code "20") (name "MOSI") (class "Default")
      (node (ref "D11") (pin "2") (pinfunction "2_2") (pintype "passive"))
      (node (ref "J1") (pin "14") (pinfunction "14_14") (pintype "bidirectional"))
      (node (ref "J4") (pin "P3") (pinfunction "CMD_P3") (pintype "bidirectional"))
      (node (ref "R7") (pin "1") (pinfunction "1_1") (pintype "passive"))
      (node (ref "TP7") (pin "TP") (pinfunction "TP_TP") (pintype "input"))
      (node (ref "U1") (pin "5") (pinfunction "DI(IO0)_5") (pintype "bidirectional"))
      (node (ref "U2") (pin "7") (pinfunction "IO7_7") (pintype "bidirectional"))
    )
    (net (code "21") (name "Net-(CHG_LED-PadC)") (class "Default")
      (node (ref "CHG_LED") (pin "C") (pinfunction "C_C") (pintype "passive"))
      (node (ref "R1_BAT") (pin "2") (pinfunction "2_2") (pintype "passive"))
    )
    (net (code "22") (name "Net-(D2-CATHODE)") (class "Default")
      (node (ref "C1_BAT1") (pin "1") (pinfunction "1_1") (pintype "passive"))
      (node (ref "D2") (pin "1") (pinfunction "CATHODE_1") (pintype "bidirectional"))
      (node (ref "IC4") (pin "1") (pinfunction "VIN_1") (pintype "bidirectional"))
      (node (ref "IC4") (pin "3") (pinfunction "CE_3") (pintype "bidirectional"))
      (node (ref "Q1") (pin "2") (pinfunction "S_2") (pintype "bidirectional"))
    )
    (net (code "23") (name "Net-(D3-A)") (class "Default")
      (node (ref "C4") (pin "1") (pinfunction "1_1") (pintype "passive"))
      (node (ref "D3") (pin "2") (pinfunction "A_2") (pintype "bidirectional"))
      (node (ref "D4") (pin "1") (pinfunction "K_1") (pintype "bidirectional"))
    )
    (net (code "24") (name "Net-(D7-CATHODE)") (class "Default")
      (node (ref "D7") (pin "1") (pinfunction "CATHODE_1") (pintype "bidirectional"))
      (node (ref "R_CAPACITOR") (pin "2") (pinfunction "2_2") (pintype "passive"))
    )
    (net (code "25") (name "Net-(EPD_C1-Pad1)") (class "Default")
      (node (ref "EPD_C1") (pin "1") (pinfunction "1_1") (pintype "passive"))
      (node (ref "J1") (pin "4") (pinfunction "4_4") (pintype "bidirectional"))
    )
    (net (code "26") (name "Net-(EPD_C2-Pad1)") (class "Default")
      (node (ref "EPD_C2") (pin "1") (pinfunction "1_1") (pintype "passive"))
      (node (ref "J1") (pin "5") (pinfunction "5_5") (pintype "bidirectional"))
    )
    (net (code "27") (name "Net-(EPD_C6-Pad1)") (class "Default")
      (node (ref "EPD_C6") (pin "1") (pinfunction "1_1") (pintype "passive"))
      (node (ref "J1") (pin "18") (pinfunction "18_18") (pintype "bidirectional"))
    )
    (net (code "28") (name "Net-(EPD_C7-Pad1)") (class "Default")
      (node (ref "EPD_C7") (pin "1") (pinfunction "1_1") (pintype "passive"))
      (node (ref "J1") (pin "19") (pinfunction "19_19") (pintype "bidirectional"))
    )
    (net (code "29") (name "Net-(EPD_C8-Pad1)") (class "Default")
      (node (ref "EPD_C8") (pin "1") (pinfunction "1_1") (pintype "passive"))
      (node (ref "J1") (pin "20") (pinfunction "20_20") (pintype "bidirectional"))
    )
    (net (code "30") (name "Net-(EPD_C10-Pad1)") (class "Default")
      (node (ref "EPD_C10") (pin "1") (pinfunction "1_1") (pintype "passive"))
      (node (ref "J1") (pin "22") (pinfunction "22_22") (pintype "bidirectional"))
    )
    (net (code "31") (name "Net-(EPD_C12-Pad1)") (class "Default")
      (node (ref "EPD_C12") (pin "1") (pinfunction "1_1") (pintype "passive"))
      (node (ref "J1") (pin "24") (pinfunction "24_24") (pintype "bidirectional"))
    )
    (net (code "32") (name "Net-(IC1-CT)") (class "Default")
      (node (ref "C_DELAY") (pin "1") (pinfunction "1_1") (pintype "passive"))
      (node (ref "IC1") (pin "5") (pinfunction "CT_5") (pintype "bidirectional"))
    )
    (net (code "33") (name "Net-(J2-PadA5)") (class "Default")
      (node (ref "J2") (pin "A5") (pinfunction "A5_A5") (pintype "bidirectional"))
      (node (ref "R2-USB1") (pin "2") (pinfunction "2_2") (pintype "passive"))
    )
    (net (code "34") (name "Net-(J2-PadB5)") (class "Default")
      (node (ref "J2") (pin "B5") (pinfunction "B5_B5") (pintype "bidirectional"))
      (node (ref "R2-USB") (pin "1") (pinfunction "1_1") (pintype "passive"))
    )
    (net (code "35") (name "Net-(MCP73831-PROG)") (class "Default")
      (node (ref "MCP73831") (pin "5") (pinfunction "PROG_5") (pintype "input"))
      (node (ref "R2_BAT") (pin "2") (pinfunction "2_2") (pintype "passive"))
    )
    (net (code "36") (name "Net-(MCP73831-STAT)") (class "Default")
      (node (ref "MCP73831") (pin "1") (pinfunction "STAT_1") (pintype "output"))
      (node (ref "R1_BAT") (pin "1") (pinfunction "1_1") (pintype "passive"))
    )
    (net (code "37") (name "PREVGH") (class "Default")
      (node (ref "D5") (pin "1") (pinfunction "K_1") (pintype "bidirectional"))
      (node (ref "EPD_C9") (pin "1") (pinfunction "1_1") (pintype "passive"))
      (node (ref "J1") (pin "21") (pinfunction "21_21") (pintype "bidirectional"))
    )
    (net (code "38") (name "PREVGL") (class "Default")
      (node (ref "D4") (pin "2") (pinfunction "A_2") (pintype "bidirectional"))
      (node (ref "EPD_C11") (pin "1") (pinfunction "1_1") (pintype "passive"))
      (node (ref "J1") (pin "23") (pinfunction "23_23") (pintype "bidirectional"))
    )
    (net (code "39") (name "RESE") (class "Default")
      (node (ref "J1") (pin "3") (pinfunction "3_3") (pintype "bidirectional"))
      (node (ref "Q3") (pin "2") (pinfunction "S_2") (pintype "bidirectional"))
      (node (ref "R3") (pin "1") (pinfunction "1_1") (pintype "passive"))
    )
    (net (code "40") (name "RESE'") (class "Default")
      (node (ref "R2") (pin "2") (pinfunction "2_2") (pintype "passive"))
      (node (ref "R3") (pin "2") (pinfunction "2_2") (pintype "passive"))
      (node (ref "SJ1") (pin "2") (pinfunction "2_2") (pintype "passive"))
    )
    (net (code "41") (name "RESET") (class "Default")
      (node (ref "C5") (pin "1") (pinfunction "1_1") (pintype "passive"))
      (node (ref "IC1") (pin "1") (pinfunction "VOUT_1") (pintype "bidirectional"))
      (node (ref "RESET_BUTTON") (pin "3") (pinfunction "3_3") (pintype "passive"))
      (node (ref "RESET_BUTTON") (pin "4") (pinfunction "4_4") (pintype "passive"))
      (node (ref "R_RESET") (pin "2") (pinfunction "2_2") (pintype "passive"))
      (node (ref "U2") (pin "3") (pinfunction "EN_3") (pintype "input"))
    )
    (net (code "42") (name "RTC_RST") (class "Default")
      (node (ref "U2") (pin "16") (pinfunction "IO18_16") (pintype "bidirectional"))
      (node (ref "U3") (pin "4") (pinfunction "~{RST}_4") (pintype "input"))
    )
    (net (code "43") (name "RX") (class "Default")
      (node (ref "TP2") (pin "TP") (pinfunction "TP_TP") (pintype "input"))
      (node (ref "U2") (pin "24") (pinfunction "RXD0/GPIO17_24") (pintype "bidirectional"))
    )
    (net (code "44") (name "SCK") (class "Default")
      (node (ref "D10") (pin "2") (pinfunction "2_2") (pintype "passive"))
      (node (ref "J1") (pin "13") (pinfunction "13_13") (pintype "bidirectional"))
      (node (ref "J4") (pin "P5") (pinfunction "CLK_P5") (pintype "bidirectional"))
      (node (ref "R6") (pin "1") (pinfunction "1_1") (pintype "passive"))
      (node (ref "TP8") (pin "TP") (pinfunction "TP_TP") (pintype "input"))
      (node (ref "U1") (pin "6") (pinfunction "CLK_6") (pintype "input"))
      (node (ref "U2") (pin "6") (pinfunction "IO6_6") (pintype "bidirectional"))
    )
    (net (code "45") (name "SCL") (class "Default")
      (node (ref "J3") (pin "4") (pinfunction "4_4") (pintype "passive"))
      (node (ref "R2_PINH") (pin "1") (pinfunction "1_1") (pintype "passive"))
      (node (ref "SENSOR2") (pin "4") (pinfunction "SCK_4") (pintype "input"))
      (node (ref "U2") (pin "20") (pinfunction "IO22_20") (pintype "bidirectional"))
      (node (ref "U3") (pin "16") (pinfunction "SCL_16") (pintype "input"))
      (node (ref "U4") (pin "7") (pinfunction "SCL_7") (pintype "input"))
    )
    (net (code "46") (name "SDA") (class "Default")
      (node (ref "J3") (pin "3") (pinfunction "3_3") (pintype "passive"))
      (node (ref "R1_PINH") (pin "1") (pinfunction "1_1") (pintype "passive"))
      (node (ref "SENSOR2") (pin "3") (pinfunction "SDI_3") (pintype "bidirectional"))
      (node (ref "U2") (pin "19") (pinfunction "IO21_19") (pintype "bidirectional"))
      (node (ref "U3") (pin "15") (pinfunction "SDA_15") (pintype "bidirectional"))
      (node (ref "U4") (pin "8") (pinfunction "SDA_8") (pintype "bidirectional"))
    )
    (net (code "47") (name "SRC") (class "Default")
      (node (ref "C4") (pin "2") (pinfunction "2_2") (pintype "passive"))
      (node (ref "D5") (pin "2") (pinfunction "A_2") (pintype "bidirectional"))
      (node (ref "L1") (pin "1") (pinfunction "1_1") (pintype "passive"))
      (node (ref "Q3") (pin "3") (pinfunction "D_3") (pintype "bidirectional"))
    )
    (net (code "48") (name "SS_SD") (class "Default")
      (node (ref "D8") (pin "2") (pinfunction "2_2") (pintype "passive"))
      (node (ref "J4") (pin "P2") (pinfunction "CD/DAT3_P2") (pintype "bidirectional"))
      (node (ref "R10") (pin "1") (pinfunction "1_1") (pintype "passive"))
      (node (ref "U2") (pin "4") (pinfunction "IO4_4") (pintype "bidirectional"))
    )
    (net (code "49") (name "TX") (class "Default")
      (node (ref "TP1") (pin "TP") (pinfunction "TP_TP") (pintype "input"))
      (node (ref "U2") (pin "25") (pinfunction "TXD0/GPIO16_25") (pintype "bidirectional"))
    )
    (net (code "50") (name "USB_D+") (class "Default")
      (node (ref "D1") (pin "1") (pinfunction "I/O1_1_1") (pintype "bidirectional"))
      (node (ref "U2") (pin "14") (pinfunction "IO13_14") (pintype "bidirectional"))
    )
    (net (code "51") (name "USB_D-") (class "Default")
      (node (ref "D1") (pin "3") (pinfunction "I/O2_1_3") (pintype "bidirectional"))
      (node (ref "U2") (pin "13") (pinfunction "IO12_13") (pintype "bidirectional"))
    )
    (net (code "52") (name "VBAT") (class "Default")
      (node (ref "C2_BAT") (pin "1") (pinfunction "1_1") (pintype "passive"))
      (node (ref "MCP73831") (pin "3") (pinfunction "VBAT_3") (pintype "power_in"))
      (node (ref "Q1") (pin "3") (pinfunction "D_3") (pintype "bidirectional"))
      (node (ref "TP3") (pin "TP") (pinfunction "TP_TP") (pintype "input"))
      (node (ref "U4") (pin "2") (pinfunction "CELL_2") (pintype "power_in"))
      (node (ref "U4") (pin "3") (pinfunction "VDD_3") (pintype "power_in"))
    )
    (net (code "53") (name "VBUS") (class "Default")
      (node (ref "C1_BAT") (pin "1") (pinfunction "1_1") (pintype "passive"))
      (node (ref "C4_USB") (pin "1") (pinfunction "1_1") (pintype "passive"))
      (node (ref "C5_USB") (pin "1") (pinfunction "1_1") (pintype "passive"))
      (node (ref "CHG_LED") (pin "A") (pinfunction "A_A") (pintype "passive"))
      (node (ref "D1") (pin "5") (pinfunction "VBUS_5") (pintype "bidirectional"))
      (node (ref "D2") (pin "2") (pinfunction "ANODE_2") (pintype "bidirectional"))
      (node (ref "MCP73831") (pin "4") (pinfunction "VIN_4") (pintype "power_in"))
      (node (ref "PFMF.050.1") (pin "2") (pinfunction "2_2") (pintype "passive"))
      (node (ref "Q1") (pin "1") (pinfunction "G_1") (pintype "bidirectional"))
      (node (ref "R1_PWRUSB") (pin "2") (pinfunction "2_2") (pintype "passive"))
      (node (ref "TP14") (pin "TP") (pinfunction "TP_TP") (pintype "input"))
    )
    (net (code "54") (name "VRTC") (class "Default")
      (node (ref "C10_SUPERCAP") (pin "2") (pinfunction "2_2") (pintype "passive"))
      (node (ref "C8") (pin "1") (pinfunction "1_1") (pintype "passive"))
      (node (ref "R_CAPACITOR") (pin "1") (pinfunction "1_1") (pintype "passive"))
      (node (ref "U3") (pin "14") (pinfunction "VBAT_14") (pintype "power_in"))
    )
    (net (code "55") (name "VUSB") (class "Default")
      (node (ref "J2") (pin "A4") (pinfunction "A4_A4") (pintype "bidirectional"))
      (node (ref "J2") (pin "A9") (pinfunction "A9_A9") (pintype "bidirectional"))
      (node (ref "J2") (pin "B4") (pinfunction "B4_B4") (pintype "bidirectional"))
      (node (ref "J2") (pin "B9") (pinfunction "B9_B9") (pintype "bidirectional"))
      (node (ref "PFMF.050.1") (pin "1") (pinfunction "1_1") (pintype "passive"))
    )
    (net (code "56") (name "unconnected-(IC1-NC-Pad4)") (class "Default")
      (node (ref "IC1") (pin "4") (pinfunction "NC_4") (pintype "no_connect"))
    )
    (net (code "57") (name "unconnected-(IC4-NC-Pad4)") (class "Default")
      (node (ref "IC4") (pin "4") (pinfunction "NC_4") (pintype "no_connect"))
    )
    (net (code "58") (name "unconnected-(J1-Pad1)") (class "Default")
      (node (ref "J1") (pin "1") (pinfunction "1_1") (pintype "bidirectional"))
    )
    (net (code "59") (name "unconnected-(J1-Pad6)") (class "Default")
      (node (ref "J1") (pin "6") (pinfunction "6_6") (pintype "bidirectional"))
    )
    (net (code "60") (name "unconnected-(J1-Pad7)") (class "Default")
      (node (ref "J1") (pin "7") (pinfunction "7_7") (pintype "bidirectional"))
    )
    (net (code "61") (name "unconnected-(J2-PadA8)") (class "Default")
      (node (ref "J2") (pin "A8") (pinfunction "A8_A8") (pintype "bidirectional"))
    )
    (net (code "62") (name "unconnected-(J2-PadB8)") (class "Default")
      (node (ref "J2") (pin "B8") (pinfunction "B8_B8") (pintype "bidirectional"))
    )
    (net (code "63") (name "unconnected-(J4-DAT1-PadP8)") (class "Default")
      (node (ref "J4") (pin "P8") (pinfunction "DAT1_P8") (pintype "bidirectional"))
    )
    (net (code "64") (name "unconnected-(J4-DAT2-PadP1)") (class "Default")
      (node (ref "J4") (pin "P1") (pinfunction "DAT2_P1") (pintype "bidirectional"))
    )
    (net (code "65") (name "unconnected-(J4-DETECTION_1-PadS1)") (class "Default")
      (node (ref "J4") (pin "S1") (pinfunction "DETECTION_1_S1") (pintype "bidirectional"))
    )
    (net (code "66") (name "unconnected-(J4-DETECTION_2-PadS2)") (class "Default")
      (node (ref "J4") (pin "S2") (pinfunction "DETECTION_2_S2") (pintype "bidirectional"))
    )
    (net (code "67") (name "unconnected-(U2-NC-Pad22)") (class "Default")
      (node (ref "U2") (pin "22") (pinfunction "NC_22") (pintype "no_connect"))
    )
    (net (code "68") (name "unconnected-(U4-~{ALERT}-Pad5)") (class "Default")
      (node (ref "U4") (pin "5") (pinfunction "~{ALERT}_5") (pintype "output"))
    )
  )
)
